# DigitalMaze.net
KiCad netlist of a schematic drawn in Altium Designer
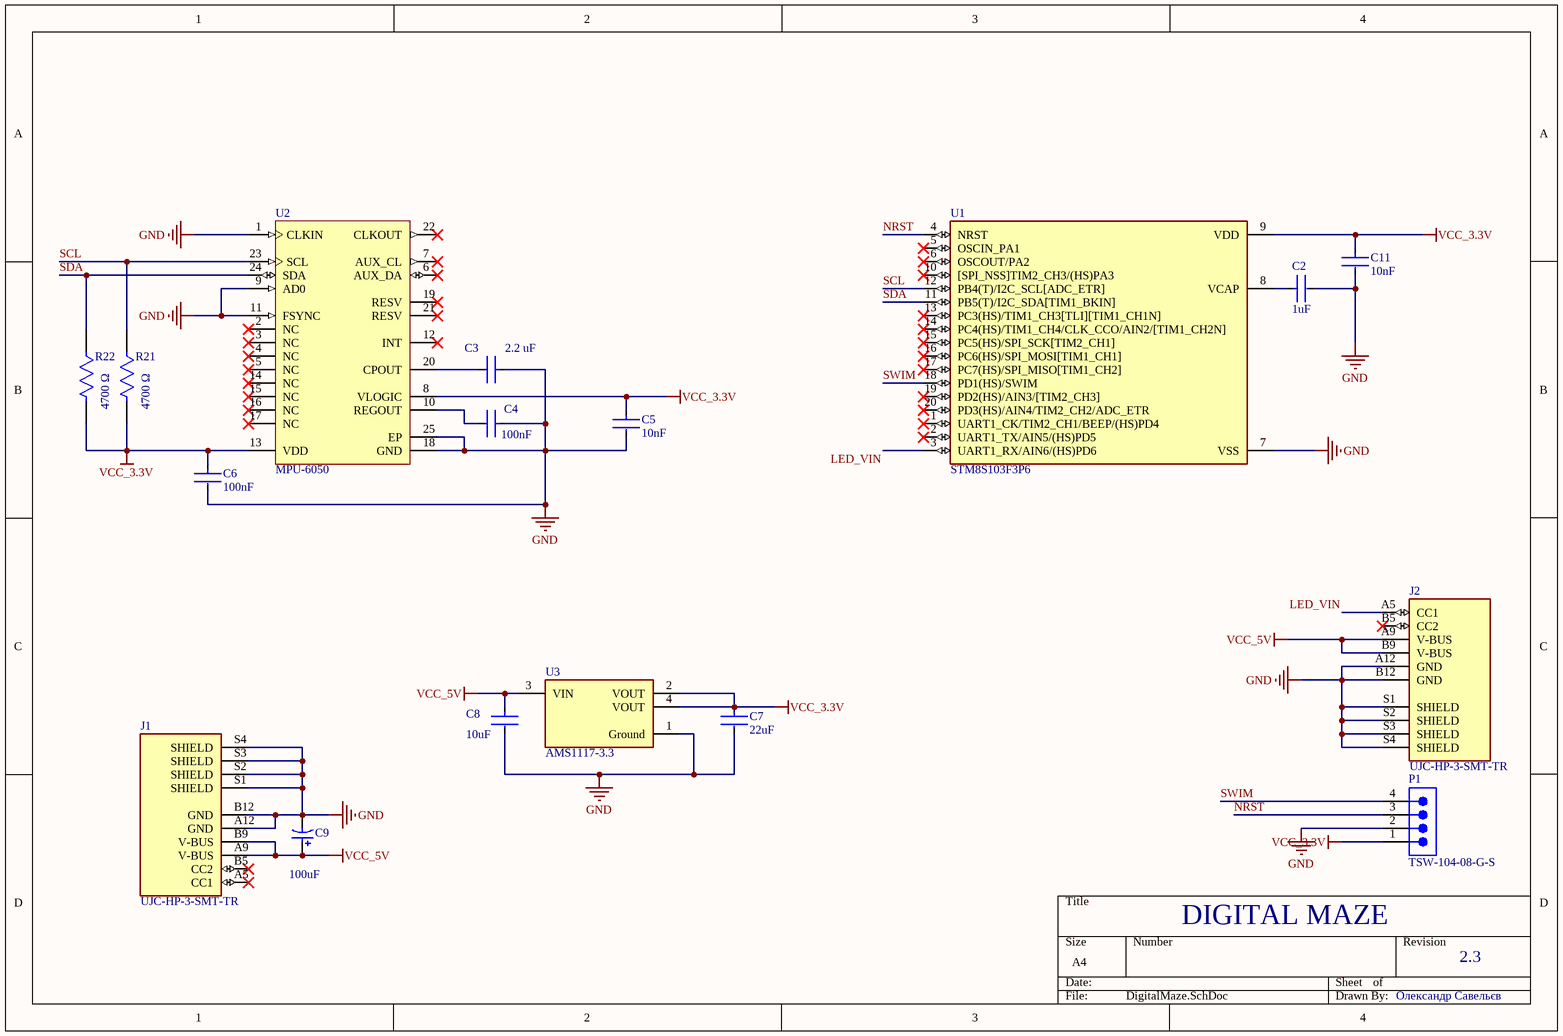
[diagram p0: DigitalMaze.SchDoc]

(export (version "E")
  (design (tool "Eeschema 10.0.6"))
  (components
    (comp (ref "C2")
      (value "1uF")
      (footprint "FP-GCG31C-0_3-IPC_A")
      (libsource (lib "Altium Content Vault") (part "02cd4be3c70576c341d710602a673aa"))
    )
    (comp (ref "C3")
      (value "2.2 uF")
      (footprint "FP-CGA6P-IPC_C")
      (description "Cap Ceramic 2.2uF 50V X7R 10% Pad SMD 1210 +125°C Automotive T/R")
      (fields (field (name "TOLERANCE") "10%"))
      (libsource (lib "Altium Content Vault") (part "b4654b650e69147ec39a6b967a45e02"))
    )
    (comp (ref "C4")
      (value "100nF")
      (footprint "FP-GRM033-0_03-IPC_A")
      (description "Chip Multilayer Ceramic Capacitors for General Purpose, 0201, 0.10uF, X6S, 22%, 10%, 4V")
      (fields (field (name "TOLERANCE") "10%"))
      (libsource (lib "Altium Content Vault") (part "b4654b650e69147ec39a6b967a45e02"))
    )
    (comp (ref "C5")
      (value "10nF")
      (footprint "FP-GRM155-0_05-IPC_C")
      (description "Chip Multilayer Ceramic Capacitors for General Purpose, 0402, 10000pF, X7R, 15%, 10%, 50V")
      (fields (field (name "TOLERANCE") "10%") (field (name "VOLTAGE") "25V"))
      (libsource (lib "Altium Content Vault") (part "02cd4be3c70576c341d710602a673aa"))
    )
    (comp (ref "C6")
      (value "100nF")
      (footprint "FP-GRM033-0_03-IPC_A")
      (description "Chip Multilayer Ceramic Capacitors for General Purpose, 0201, 0.10uF, X6S, 22%, 10%, 4V")
      (fields (field (name "TOLERANCE") "10%"))
      (libsource (lib "Altium Content Vault") (part "b4654b650e69147ec39a6b967a45e02"))
    )
    (comp (ref "C7")
      (value "22uF")
      (footprint "FP-GRM188-0_2-IPC_C")
      (description "Chip Multilayer Ceramic Capacitors for General Purpose, 0603, 22uF, X5R, 15%, 20%, 10V")
      (fields (field (name "TOLERANCE") "20%"))
      (libsource (lib "Altium Content Vault") (part "11868f565c42a9108669ba33697ecf6"))
    )
    (comp (ref "C8")
      (value "10uF")
      (footprint "FP-GRM188-0_1-e0_2_0_55-IPC_A")
      (description "Chip Multilayer Ceramic Capacitors for General Purpose, 0603, 10uF, X5R, 15%, 20%, 6.3V")
      (fields (field (name "VOLTAGE") "6.3V") (field (name "TOLERANCE") "20%"))
      (libsource (lib "Altium Content Vault") (part "02cd4be3c70576c341d710602a673aa"))
    )
    (comp (ref "C9")
      (value "100uF")
      (footprint "PNSC-FK-V-D8_V")
      (fields (field (name "MANUFACTURER") "Panasonic"))
      (libsource (lib "Altium Content Vault") (part "CAP-P-2"))
    )
    (comp (ref "C11")
      (value "10nF")
      (footprint "FP-GRM155-0_05-IPC_C")
      (description "Chip Multilayer Ceramic Capacitors for General Purpose, 0402, 10000pF, X7R, 15%, 10%, 50V")
      (fields (field (name "TOLERANCE") "10%") (field (name "VOLTAGE") "25V"))
      (libsource (lib "Altium Content Vault") (part "02cd4be3c70576c341d710602a673aa"))
    )
    (comp (ref "J1")
      (value "UJC-HP-3-SMT-TR")
      (footprint "CUI_UJC-HP-3-SMT-TR")
      (libsource (lib "UJC-HP-3-SMT-TR") (part "UJC-HP-3-SMT-TR"))
    )
    (comp (ref "J2")
      (value "UJC-HP-3-SMT-TR")
      (footprint "CUI_UJC-HP-3-SMT-TR")
      (libsource (lib "") (part "UJC-HP-3-SMT-TR_1"))
    )
    (comp (ref "P1")
      (value "TSW-104-08-G-S")
      (footprint "SMTC-TSW-104-08-X-S")
      (description "0.025\" SQ Post Header, Through-hole, Vertical, -55 to 125 degC, 2.54 mm Pitch, 4-Pin, Male, RoHS")
      (fields (field (name "MANUFACTURER") "Samtec"))
      (libsource (lib "Altium Content Vault") (part "SMTC-TSW-104-08-X-S"))
    )
    (comp (ref "R21")
      (value "4700 Ω")
      (footprint "FP-RC1206-0_65-IPC_B")
      (description "RES SMD 4.7K OHM 1% 1/4W 1206")
      (fields (field (name "TOLERANCE") "1%"))
      (libsource (lib "Altium Content Vault") (part "1029c3af85768c4190bb7ad29bc67b5"))
    )
    (comp (ref "R22")
      (value "4700 Ω")
      (footprint "FP-RC1206-0_65-IPC_B")
      (description "RES SMD 4.7K OHM 1% 1/4W 1206")
      (fields (field (name "TOLERANCE") "1%"))
      (libsource (lib "Altium Content Vault") (part "1029c3af85768c4190bb7ad29bc67b5"))
    )
    (comp (ref "U1")
      (value "STM8S103F3P6")
      (footprint "SOP65P640X120-20N")
      (description "STM8 series Microcontroller IC 8-Bit 16MHz 8KB (8K x 8) FLASH 20-TSSOP")
      (fields (field (name "MF") "STMicroelectronics"))
      (libsource (lib "STM8S103F3P6") (part "STM8S103F3P6"))
    )
    (comp (ref "U2")
      (value "MPU-6050")
      (footprint "IS-QFN-24_V")
      (fields (field (name "MANUFACTURER") "InvenSense"))
      (libsource (lib "Altium Content Vault") (part "IS-MPU-6050-QFN-24"))
    )
    (comp (ref "U3")
      (value "AMS1117-3.3")
      (footprint "FP-AMS1117-IPC_C")
      (description "LDO Voltage Regulators 1A, 3.3V")
      (fields
        (field (name "OCTOPART") "https://octopart.com/ams1117-3.3-advanced+monolithic+systems-25899300")
        (field (name "MANUFACTURER") "Advanced Monolithic Systems")
      )
      (libsource (lib "Altium Content Vault") (part "8bdbb5f8e77002000e30dd2845d0354"))
    )
  )
  (nets
    (net (code "1") (name "/LED_VIN") (class "Default")
      (node (ref "J2") (pin "A5") (pinfunction "CC1_A5") (pintype "bidirectional"))
      (node (ref "U1") (pin "3") (pinfunction "UART1_RX/AIN6/(HS)PD6_3") (pintype "bidirectional"))
    )
    (net (code "2") (name "/NRST") (class "Default")
      (node (ref "P1") (pin "3") (pinfunction "3_3") (pintype "passive"))
      (node (ref "U1") (pin "4") (pinfunction "NRST_4") (pintype "bidirectional"))
    )
    (net (code "3") (name "/SCL") (class "Default")
      (node (ref "R21") (pin "1") (pinfunction "1_1") (pintype "passive"))
      (node (ref "U1") (pin "12") (pinfunction "PB4(T)/I2C_SCL[ADC_ETR]_12") (pintype "bidirectional"))
      (node (ref "U2") (pin "23") (pinfunction "SCL_23") (pintype "input"))
    )
    (net (code "4") (name "/SDA") (class "Default")
      (node (ref "R22") (pin "1") (pinfunction "1_1") (pintype "passive"))
      (node (ref "U1") (pin "11") (pinfunction "PB5(T)/I2C_SDA[TIM1_BKIN]_11") (pintype "bidirectional"))
      (node (ref "U2") (pin "24") (pinfunction "SDA_24") (pintype "bidirectional"))
    )
    (net (code "5") (name "/SWIM") (class "Default")
      (node (ref "P1") (pin "4") (pinfunction "4_4") (pintype "passive"))
      (node (ref "U1") (pin "18") (pinfunction "PD1(HS)/SWIM_18") (pintype "bidirectional"))
    )
    (net (code "6") (name "GND") (class "Default")
      (node (ref "C11") (pin "2") (pinfunction "2_2") (pintype "passive"))
      (node (ref "C2") (pin "2") (pinfunction "2_2") (pintype "passive"))
      (node (ref "C3") (pin "1") (pinfunction "1_1") (pintype "passive"))
      (node (ref "C4") (pin "1") (pinfunction "1_1") (pintype "passive"))
      (node (ref "C5") (pin "2") (pinfunction "2_2") (pintype "passive"))
      (node (ref "C6") (pin "2") (pinfunction "2_2") (pintype "passive"))
      (node (ref "C7") (pin "2") (pinfunction "2_2") (pintype "passive"))
      (node (ref "C8") (pin "2") (pinfunction "2_2") (pintype "passive"))
      (node (ref "C9") (pin "2") (pinfunction "2_2") (pintype "passive"))
      (node (ref "J1") (pin "A12") (pinfunction "GND_A12") (pintype "power_in"))
      (node (ref "J1") (pin "B12") (pinfunction "GND_B12") (pintype "power_in"))
      (node (ref "J1") (pin "S1") (pinfunction "SHIELD_S1") (pintype "passive"))
      (node (ref "J1") (pin "S2") (pinfunction "SHIELD_S2") (pintype "passive"))
      (node (ref "J1") (pin "S3") (pinfunction "SHIELD_S3") (pintype "passive"))
      (node (ref "J1") (pin "S4") (pinfunction "SHIELD_S4") (pintype "passive"))
      (node (ref "J2") (pin "A12") (pinfunction "GND_A12") (pintype "power_in"))
      (node (ref "J2") (pin "B12") (pinfunction "GND_B12") (pintype "power_in"))
      (node (ref "J2") (pin "S1") (pinfunction "SHIELD_S1") (pintype "passive"))
      (node (ref "J2") (pin "S2") (pinfunction "SHIELD_S2") (pintype "passive"))
      (node (ref "J2") (pin "S3") (pinfunction "SHIELD_S3") (pintype "passive"))
      (node (ref "J2") (pin "S4") (pinfunction "SHIELD_S4") (pintype "passive"))
      (node (ref "P1") (pin "2") (pinfunction "2_2") (pintype "passive"))
      (node (ref "U1") (pin "7") (pinfunction "VSS_7") (pintype "power_in"))
      (node (ref "U2") (pin "1") (pinfunction "CLKIN_1") (pintype "input"))
      (node (ref "U2") (pin "11") (pinfunction "FSYNC_11") (pintype "input"))
      (node (ref "U2") (pin "18") (pinfunction "GND_18") (pintype "power_in"))
      (node (ref "U2") (pin "25") (pinfunction "EP_25") (pintype "power_in"))
      (node (ref "U2") (pin "9") (pinfunction "AD0_9") (pintype "input"))
      (node (ref "U3") (pin "1") (pinfunction "Ground_1") (pintype "power_in"))
    )
    (net (code "7") (name "Net-(U1-VCAP)") (class "Default")
      (node (ref "C2") (pin "1") (pinfunction "1_1") (pintype "passive"))
      (node (ref "U1") (pin "8") (pinfunction "VCAP_8") (pintype "passive"))
    )
    (net (code "8") (name "Net-(U2-CPOUT)") (class "Default")
      (node (ref "C3") (pin "2") (pinfunction "2_2") (pintype "passive"))
      (node (ref "U2") (pin "20") (pinfunction "CPOUT_20") (pintype "passive"))
    )
    (net (code "9") (name "Net-(U2-REGOUT)") (class "Default")
      (node (ref "C4") (pin "2") (pinfunction "2_2") (pintype "passive"))
      (node (ref "U2") (pin "10") (pinfunction "REGOUT_10") (pintype "passive"))
    )
    (net (code "10") (name "VCC_3.3V") (class "Default")
      (node (ref "C11") (pin "1") (pinfunction "1_1") (pintype "passive"))
      (node (ref "C5") (pin "1") (pinfunction "1_1") (pintype "passive"))
      (node (ref "C6") (pin "1") (pinfunction "1_1") (pintype "passive"))
      (node (ref "C7") (pin "1") (pinfunction "1_1") (pintype "passive"))
      (node (ref "P1") (pin "1") (pinfunction "1_1") (pintype "passive"))
      (node (ref "R21") (pin "2") (pinfunction "2_2") (pintype "passive"))
      (node (ref "R22") (pin "2") (pinfunction "2_2") (pintype "passive"))
      (node (ref "U1") (pin "9") (pinfunction "VDD_9") (pintype "power_in"))
      (node (ref "U2") (pin "13") (pinfunction "VDD_13") (pintype "power_in"))
      (node (ref "U2") (pin "8") (pinfunction "VLOGIC_8") (pintype "power_in"))
      (node (ref "U3") (pin "2") (pinfunction "VOUT_2") (pintype "passive"))
      (node (ref "U3") (pin "4") (pinfunction "VOUT_4") (pintype "passive"))
    )
    (net (code "11") (name "VCC_5V") (class "Default")
      (node (ref "C8") (pin "1") (pinfunction "1_1") (pintype "passive"))
      (node (ref "C9") (pin "1") (pinfunction "1_1") (pintype "passive"))
      (node (ref "J1") (pin "A9") (pinfunction "V-BUS_A9") (pintype "power_in"))
      (node (ref "J1") (pin "B9") (pinfunction "V-BUS_B9") (pintype "power_in"))
      (node (ref "J2") (pin "A9") (pinfunction "V-BUS_A9") (pintype "power_in"))
      (node (ref "J2") (pin "B9") (pinfunction "V-BUS_B9") (pintype "power_in"))
      (node (ref "U3") (pin "3") (pinfunction "VIN_3") (pintype "power_in"))
    )
    (net (code "12") (name "unconnected-(J1-CC1-PadA5)") (class "Default")
      (node (ref "J1") (pin "A5") (pinfunction "CC1_A5") (pintype "bidirectional+no_connect"))
    )
    (net (code "13") (name "unconnected-(J1-CC2-PadB5)") (class "Default")
      (node (ref "J1") (pin "B5") (pinfunction "CC2_B5") (pintype "bidirectional+no_connect"))
    )
    (net (code "14") (name "unconnected-(J2-CC2-PadB5)") (class "Default")
      (node (ref "J2") (pin "B5") (pinfunction "CC2_B5") (pintype "bidirectional+no_connect"))
    )
    (net (code "15") (name "unconnected-(U1-OSCIN_PA1-Pad5)") (class "Default")
      (node (ref "U1") (pin "5") (pinfunction "OSCIN_PA1_5") (pintype "bidirectional+no_connect"))
    )
    (net (code "16") (name "unconnected-(U1-OSCOUT{slash}PA2-Pad6)") (class "Default")
      (node (ref "U1") (pin "6") (pinfunction "OSCOUT/PA2_6") (pintype "bidirectional+no_connect"))
    )
    (net (code "17") (name "unconnected-(U1-PC3(HS){slash}TIM1_CH3[TLI][TIM1_CH1N]-Pad13)") (class "Default")
      (node (ref "U1") (pin "13") (pinfunction "PC3(HS)/TIM1_CH3[TLI][TIM1_CH1N]_13") (pintype "bidirectional+no_connect"))
    )
    (net (code "18") (name "unconnected-(U1-PC4(HS){slash}TIM1_CH4{slash}CLK_CCO{slash}AIN2{slash}[TIM1_CH2N]-Pad14)") (class "Default")
      (node (ref "U1") (pin "14") (pinfunction "PC4(HS)/TIM1_CH4/CLK_CCO/AIN2/[TIM1_CH2N]_14") (pintype "bidirectional+no_connect"))
    )
    (net (code "19") (name "unconnected-(U1-PC5(HS){slash}SPI_SCK[TIM2_CH1]-Pad15)") (class "Default")
      (node (ref "U1") (pin "15") (pinfunction "PC5(HS)/SPI_SCK[TIM2_CH1]_15") (pintype "bidirectional+no_connect"))
    )
    (net (code "20") (name "unconnected-(U1-PC6(HS){slash}SPI_MOSI[TIM1_CH1]-Pad16)") (class "Default")
      (node (ref "U1") (pin "16") (pinfunction "PC6(HS)/SPI_MOSI[TIM1_CH1]_16") (pintype "bidirectional+no_connect"))
    )
    (net (code "21") (name "unconnected-(U1-PC7(HS){slash}SPI_MISO[TIM1_CH2]-Pad17)") (class "Default")
      (node (ref "U1") (pin "17") (pinfunction "PC7(HS)/SPI_MISO[TIM1_CH2]_17") (pintype "bidirectional+no_connect"))
    )
    (net (code "22") (name "unconnected-(U1-PD2(HS){slash}AIN3{slash}[TIM2_CH3]-Pad19)") (class "Default")
      (node (ref "U1") (pin "19") (pinfunction "PD2(HS)/AIN3/[TIM2_CH3]_19") (pintype "bidirectional+no_connect"))
    )
    (net (code "23") (name "unconnected-(U1-PD3(HS){slash}AIN4{slash}TIM2_CH2{slash}ADC_ETR-Pad20)") (class "Default")
      (node (ref "U1") (pin "20") (pinfunction "PD3(HS)/AIN4/TIM2_CH2/ADC_ETR_20") (pintype "bidirectional+no_connect"))
    )
    (net (code "24") (name "unconnected-(U1-UART1_CK{slash}TIM2_CH1{slash}BEEP{slash}(HS)PD4-Pad1)") (class "Default")
      (node (ref "U1") (pin "1") (pinfunction "UART1_CK/TIM2_CH1/BEEP/(HS)PD4_1") (pintype "bidirectional+no_connect"))
    )
    (net (code "25") (name "unconnected-(U1-UART1_TX{slash}AIN5{slash}(HS)PD5-Pad2)") (class "Default")
      (node (ref "U1") (pin "2") (pinfunction "UART1_TX/AIN5/(HS)PD5_2") (pintype "bidirectional+no_connect"))
    )
    (net (code "26") (name "unconnected-(U1-[SPI_NSS]TIM2_CH3{slash}(HS)PA3-Pad10)") (class "Default")
      (node (ref "U1") (pin "10") (pinfunction "[SPI_NSS]TIM2_CH3/(HS)PA3_10") (pintype "bidirectional+no_connect"))
    )
    (net (code "27") (name "unconnected-(U2-AUX_CL-Pad7)") (class "Default")
      (node (ref "U2") (pin "7") (pinfunction "AUX_CL_7") (pintype "output+no_connect"))
    )
    (net (code "28") (name "unconnected-(U2-AUX_DA-Pad6)") (class "Default")
      (node (ref "U2") (pin "6") (pinfunction "AUX_DA_6") (pintype "bidirectional+no_connect"))
    )
    (net (code "29") (name "unconnected-(U2-CLKOUT-Pad22)") (class "Default")
      (node (ref "U2") (pin "22") (pinfunction "CLKOUT_22") (pintype "output+no_connect"))
    )
    (net (code "30") (name "unconnected-(U2-INT-Pad12)") (class "Default")
      (node (ref "U2") (pin "12") (pinfunction "INT_12") (pintype "open_collector+no_connect"))
    )
    (net (code "31") (name "unconnected-(U2-NC-Pad2)") (class "Default")
      (node (ref "U2") (pin "2") (pinfunction "NC_2") (pintype "passive+no_connect"))
    )
    (net (code "32") (name "unconnected-(U2-NC-Pad3)") (class "Default")
      (node (ref "U2") (pin "3") (pinfunction "NC_3") (pintype "passive+no_connect"))
    )
    (net (code "33") (name "unconnected-(U2-NC-Pad4)") (class "Default")
      (node (ref "U2") (pin "4") (pinfunction "NC_4") (pintype "passive+no_connect"))
    )
    (net (code "34") (name "unconnected-(U2-NC-Pad5)") (class "Default")
      (node (ref "U2") (pin "5") (pinfunction "NC_5") (pintype "passive+no_connect"))
    )
    (net (code "35") (name "unconnected-(U2-NC-Pad14)") (class "Default")
      (node (ref "U2") (pin "14") (pinfunction "NC_14") (pintype "passive+no_connect"))
    )
    (net (code "36") (name "unconnected-(U2-NC-Pad15)") (class "Default")
      (node (ref "U2") (pin "15") (pinfunction "NC_15") (pintype "passive+no_connect"))
    )
    (net (code "37") (name "unconnected-(U2-NC-Pad16)") (class "Default")
      (node (ref "U2") (pin "16") (pinfunction "NC_16") (pintype "passive+no_connect"))
    )
    (net (code "38") (name "unconnected-(U2-NC-Pad17)") (class "Default")
      (node (ref "U2") (pin "17") (pinfunction "NC_17") (pintype "passive+no_connect"))
    )
    (net (code "39") (name "unconnected-(U2-RESV-Pad19)") (class "Default")
      (node (ref "U2") (pin "19") (pinfunction "RESV_19") (pintype "passive+no_connect"))
    )
    (net (code "40") (name "unconnected-(U2-RESV-Pad21)") (class "Default")
      (node (ref "U2") (pin "21") (pinfunction "RESV_21") (pintype "passive+no_connect"))
    )
  )
)
